# ProProject___V1_2024-08-05.net
KiCad netlist of a schematic drawn in EasyEDA Pro
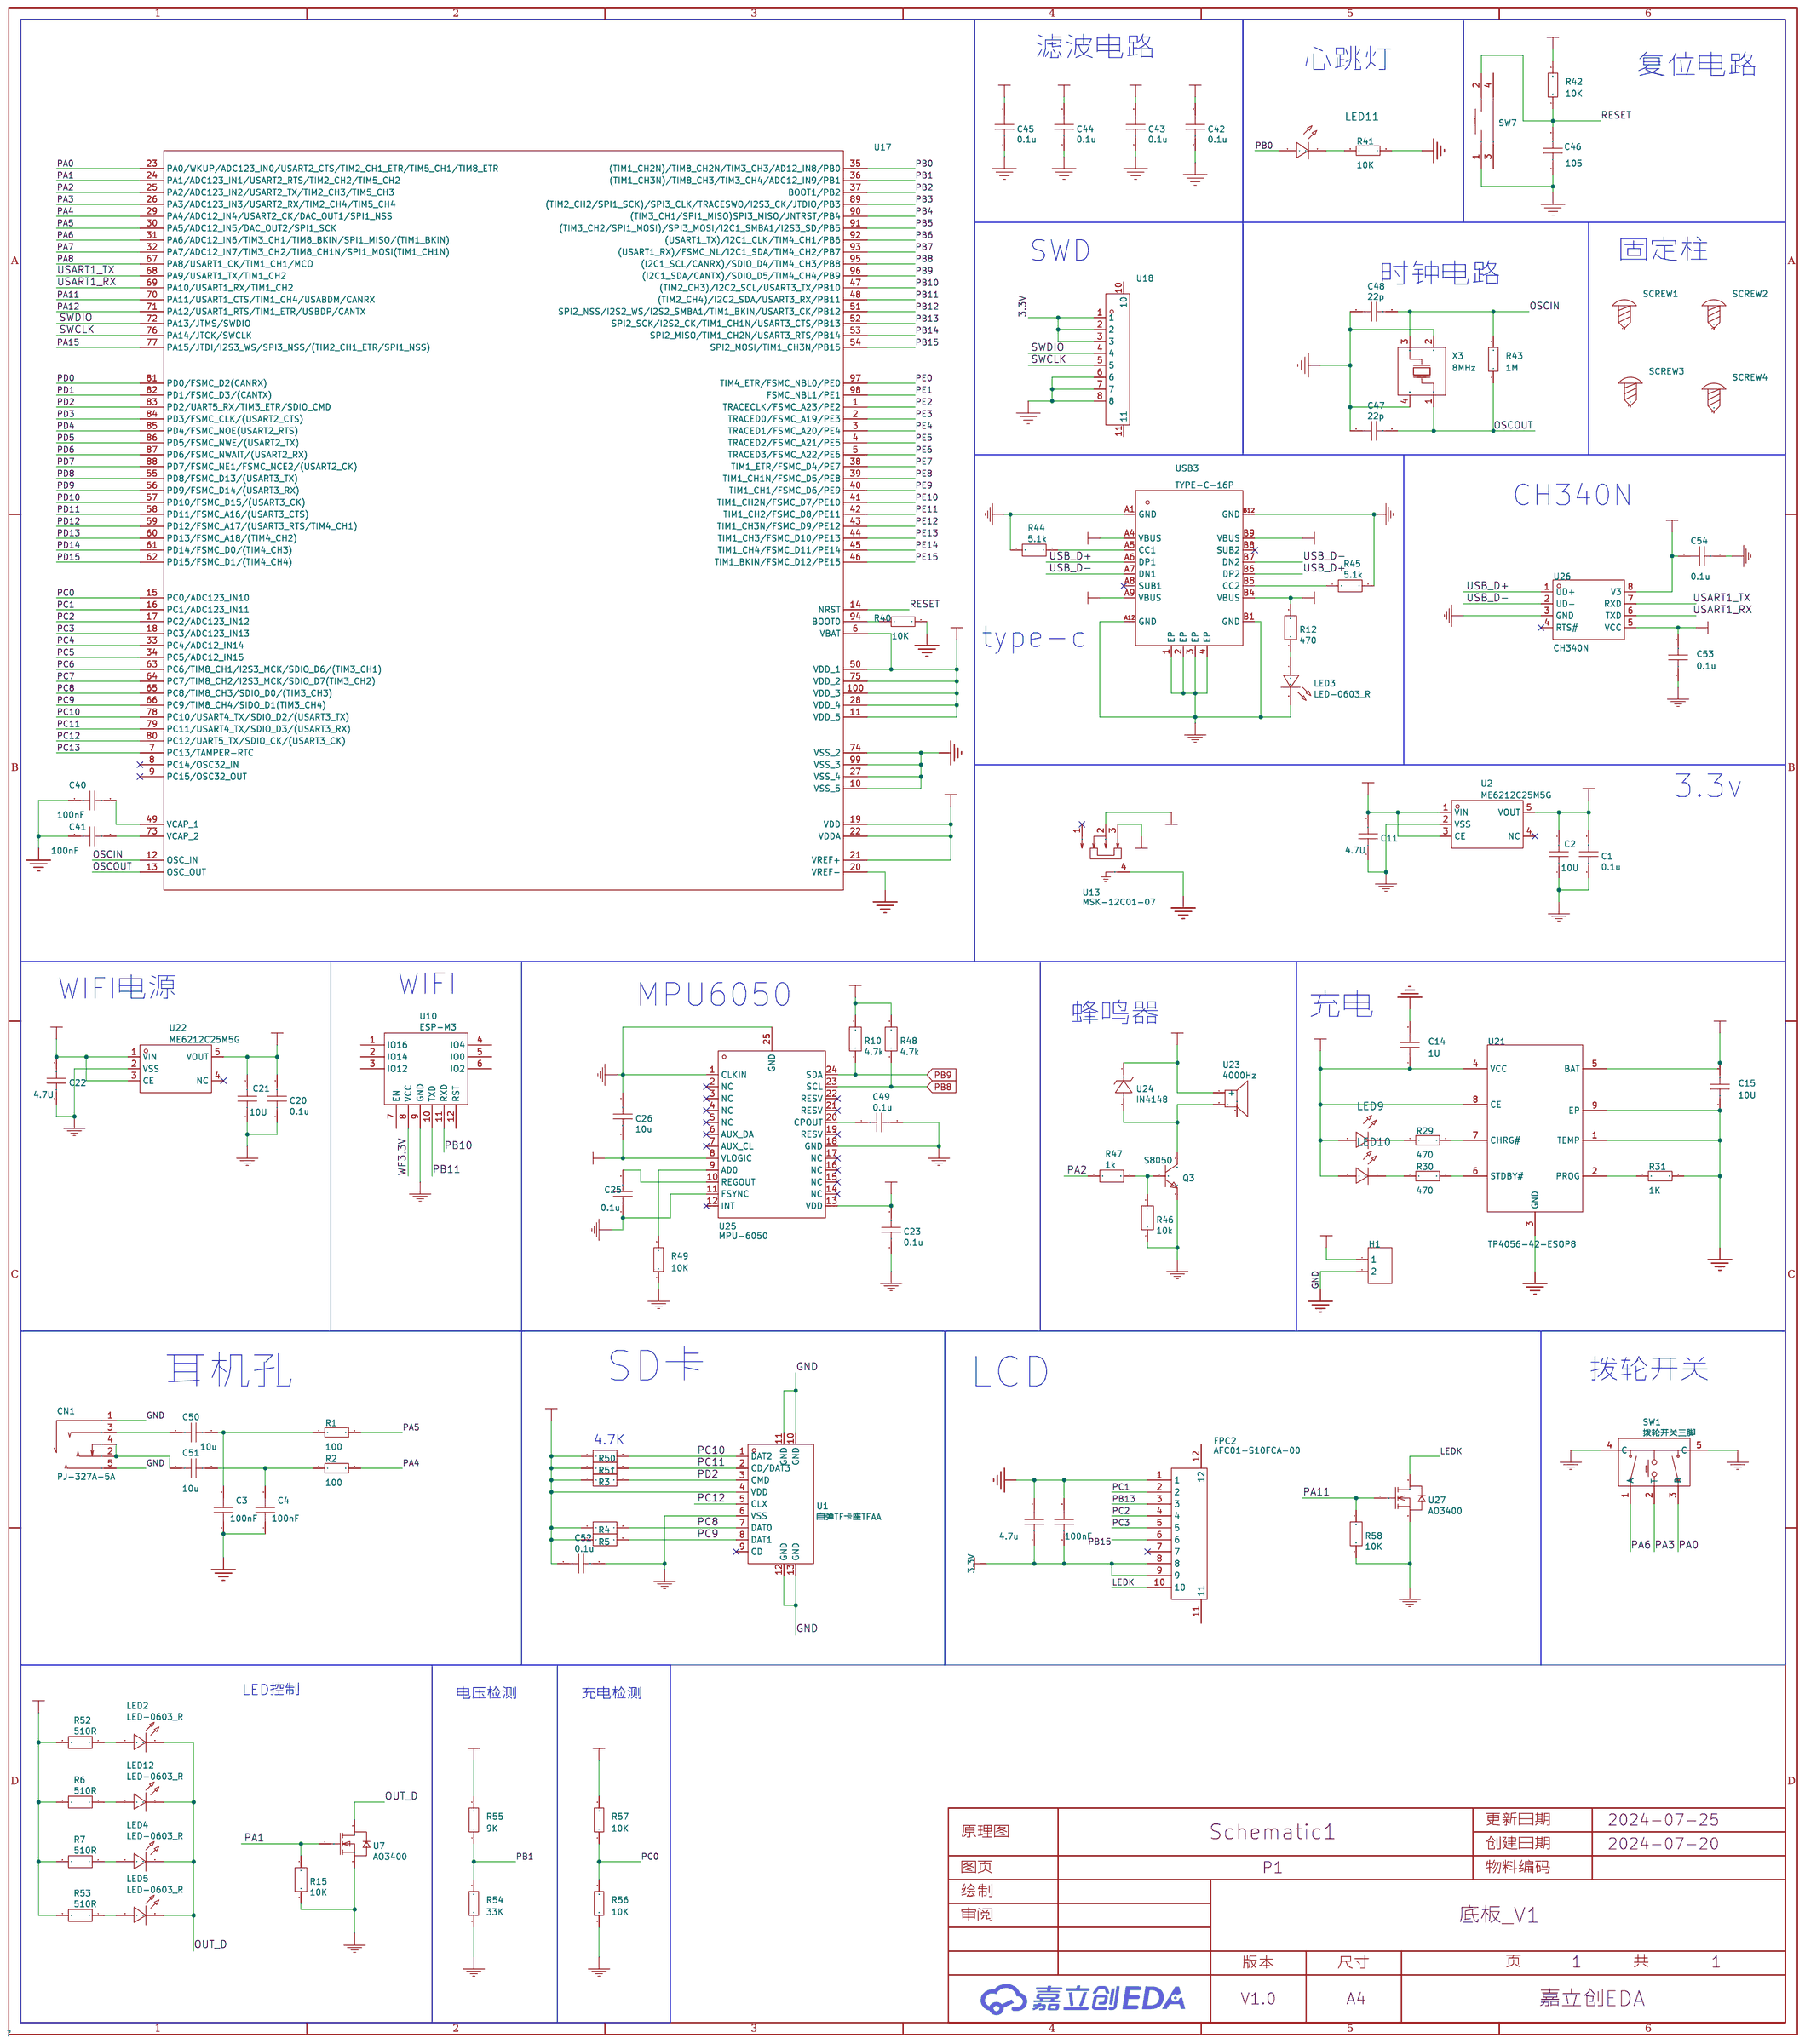
[diagram p0: schematic sheet]

(export (version "E")
  (design (tool "Eeschema 10.0.6"))
  (components
    (comp (ref "C1")
      (value "0.1u")
      (footprint "easyedapro:footprint_d063")
      (libsource (lib "easyedapro") (part "0.1u"))
    )
    (comp (ref "C2")
      (value "10U")
      (footprint "easyedapro:footprint_d063")
      (libsource (lib "easyedapro") (part "10U"))
    )
    (comp (ref "C3")
      (value "100nF")
      (footprint "easyedapro:C0603")
      (libsource (lib "easyedapro") (part "CapAcitance"))
    )
    (comp (ref "C4")
      (value "100nF")
      (footprint "easyedapro:C0603")
      (libsource (lib "easyedapro") (part "CapAcitance"))
    )
    (comp (ref "C11")
      (value "4.7U")
      (footprint "easyedapro:footprint_d063")
      (libsource (lib "easyedapro") (part "4.7U"))
    )
    (comp (ref "C14")
      (value "1U")
      (footprint "easyedapro:C0603")
      (libsource (lib "easyedapro") (part "CapAcitance"))
    )
    (comp (ref "C15")
      (value "10U")
      (footprint "easyedapro:C0603")
      (libsource (lib "easyedapro") (part "CapAcitance"))
    )
    (comp (ref "C20")
      (value "0.1u")
      (footprint "easyedapro:footprint_d063")
      (libsource (lib "easyedapro") (part "0.1u"))
    )
    (comp (ref "C21")
      (value "10U")
      (footprint "easyedapro:footprint_d063")
      (libsource (lib "easyedapro") (part "10U"))
    )
    (comp (ref "C22")
      (value "4.7U")
      (footprint "easyedapro:footprint_d063")
      (libsource (lib "easyedapro") (part "4.7U"))
    )
    (comp (ref "C23")
      (value "0.1u")
      (footprint "easyedapro:footprint_d063")
      (libsource (lib "easyedapro") (part "0.1u"))
    )
    (comp (ref "C25")
      (value "0.1u")
      (footprint "easyedapro:footprint_d063")
      (libsource (lib "easyedapro") (part "0.1u"))
    )
    (comp (ref "C26")
      (value "10u")
      (footprint "easyedapro:footprint_d063")
      (libsource (lib "easyedapro") (part "10u"))
    )
    (comp (ref "C40")
      (value "100nF")
      (footprint "easyedapro:C0603")
      (libsource (lib "easyedapro") (part "CapAcitance"))
    )
    (comp (ref "C41")
      (value "100nF")
      (footprint "easyedapro:C0603")
      (libsource (lib "easyedapro") (part "CapAcitance"))
    )
    (comp (ref "C42")
      (value "0.1u")
      (footprint "easyedapro:footprint_88df")
      (libsource (lib "easyedapro") (part "1u"))
    )
    (comp (ref "C43")
      (value "0.1u")
      (footprint "easyedapro:footprint_88df")
      (libsource (lib "easyedapro") (part "1u"))
    )
    (comp (ref "C44")
      (value "0.1u")
      (footprint "easyedapro:footprint_88df")
      (libsource (lib "easyedapro") (part "1u"))
    )
    (comp (ref "C45")
      (value "0.1u")
      (footprint "easyedapro:footprint_88df")
      (libsource (lib "easyedapro") (part "1u"))
    )
    (comp (ref "C46")
      (value "105")
      (footprint "easyedapro:footprint_88df")
      (libsource (lib "easyedapro") (part "105"))
    )
    (comp (ref "C47")
      (value "22p")
      (footprint "easyedapro:footprint_88df")
      (libsource (lib "easyedapro") (part "22p"))
    )
    (comp (ref "C48")
      (value "22p")
      (footprint "easyedapro:footprint_88df")
      (libsource (lib "easyedapro") (part "22p"))
    )
    (comp (ref "C49")
      (value "0.1u")
      (footprint "easyedapro:footprint_d063")
      (libsource (lib "easyedapro") (part "0.1u"))
    )
    (comp (ref "C50")
      (value "10u")
      (footprint "easyedapro:C0603")
      (libsource (lib "easyedapro") (part "CapAcitance"))
    )
    (comp (ref "C51")
      (value "10u")
      (footprint "easyedapro:C0603")
      (libsource (lib "easyedapro") (part "CapAcitance"))
    )
    (comp (ref "C52")
      (value "0.1u")
      (footprint "easyedapro:C0603")
      (libsource (lib "easyedapro") (part "0.1u"))
    )
    (comp (ref "C53")
      (value "0.1u")
      (footprint "easyedapro:footprint_d063")
      (libsource (lib "easyedapro") (part "0.1u"))
    )
    (comp (ref "C54")
      (value "0.1u")
      (footprint "easyedapro:footprint_d063")
      (libsource (lib "easyedapro") (part "0.1u"))
    )
    (comp (ref "C57")
      (value "100nF")
      (footprint "easyedapro:C0603")
      (libsource (lib "easyedapro") (part "CapAcitance"))
    )
    (comp (ref "C58")
      (value "4.7u")
      (footprint "easyedapro:C0603")
      (libsource (lib "easyedapro") (part "CapAcitance"))
    )
    (comp (ref "CN1")
      (value "PJ-327A-5A")
      (footprint "easyedapro:AUDIO-SMD_PJ-327A-5A")
      (description "连接器类型:3.5mm耳机座;额定电流:500mA;额定电压:30V;工作温度范围:-40°C~+80°C;")
      (fields (field (name "Manufacturer") "韩国韩荣"))
      (libsource (lib "easyedapro") (part "PJ-327A-5A"))
    )
    (comp (ref "FPC2")
      (value "AFC01-S10FCA-00")
      (footprint "easyedapro:FPC-SMD_P0.5-10P_FGS-XJ-H2.0")
      (description "锁定特性:翻盖式;触点类型:下接;触点数量:10P;间距:0.5mm;安装类型:卧贴;")
      (fields (field (name "Manufacturer") "JS(钜硕电子)"))
      (libsource (lib "easyedapro") (part "AFC01-S10FCA-00"))
    )
    (comp (ref "H1")
      (value "~")
      (footprint "easyedapro:HDR-TH_2P-P2.54-V-F")
      (libsource (lib "easyedapro") (part "Header-Female-2.54_1x2"))
    )
    (comp (ref "LED2")
      (value "LED-0603_R")
      (footprint "easyedapro:footprint_5b50")
      (fields
        (field (name "Manufacturer Part") "19-217/R6C-AL1M2VY/3T")
        (field (name "Manufacturer") "EVERLIGHT(台湾亿光)")
      )
      (libsource (lib "easyedapro") (part "LED-0603_R"))
    )
    (comp (ref "LED3")
      (value "LED-0603_R")
      (footprint "easyedapro:footprint_1210")
      (fields
        (field (name "Manufacturer Part") "19-217/R6C-AL1M2VY/3T")
        (field (name "Manufacturer") "EVERLIGHT(台湾亿光)")
      )
      (libsource (lib "easyedapro") (part "LED-0603_R"))
    )
    (comp (ref "LED4")
      (value "LED-0603_R")
      (footprint "easyedapro:footprint_5b50")
      (fields
        (field (name "Manufacturer Part") "19-217/R6C-AL1M2VY/3T")
        (field (name "Manufacturer") "EVERLIGHT(台湾亿光)")
      )
      (libsource (lib "easyedapro") (part "LED-0603_R"))
    )
    (comp (ref "LED5")
      (value "LED-0603_R")
      (footprint "easyedapro:footprint_5b50")
      (fields
        (field (name "Manufacturer Part") "19-217/R6C-AL1M2VY/3T")
        (field (name "Manufacturer") "EVERLIGHT(台湾亿光)")
      )
      (libsource (lib "easyedapro") (part "LED-0603_R"))
    )
    (comp (ref "LED9")
      (value "~")
      (footprint "easyedapro:LED_0603")
      (libsource (lib "easyedapro") (part "LED_R"))
    )
    (comp (ref "LED10")
      (value "~")
      (footprint "easyedapro:LED_0603")
      (libsource (lib "easyedapro") (part "LED_R"))
    )
    (comp (ref "LED11")
      (value "~")
      (footprint "easyedapro:LED_0603")
      (libsource (lib "easyedapro") (part "LED_R"))
    )
    (comp (ref "LED12")
      (value "LED-0603_R")
      (footprint "easyedapro:footprint_5b50")
      (fields
        (field (name "Manufacturer Part") "19-217/R6C-AL1M2VY/3T")
        (field (name "Manufacturer") "EVERLIGHT(台湾亿光)")
      )
      (libsource (lib "easyedapro") (part "LED-0603_R"))
    )
    (comp (ref "Q3")
      (value "S8050")
      (footprint "easyedapro:footprint_2907")
      (fields (field (name "Manufacturer") "集晶电子"))
      (libsource (lib "easyedapro") (part "S8050"))
    )
    (comp (ref "R1") (value "100") (footprint "easyedapro:R0805") (libsource (lib "easyedapro") (part "电阻")))
    (comp (ref "R2") (value "100") (footprint "easyedapro:R0805") (libsource (lib "easyedapro") (part "电阻")))
    (comp (ref "R3") (value "1k") (footprint "easyedapro:R0805") (libsource (lib "easyedapro") (part "1k")))
    (comp (ref "R4") (value "1k") (footprint "easyedapro:R0805") (libsource (lib "easyedapro") (part "1k")))
    (comp (ref "R5") (value "1k") (footprint "easyedapro:R0805") (libsource (lib "easyedapro") (part "1k")))
    (comp (ref "R6")
      (value "510R")
      (footprint "easyedapro:footprint_4dfc")
      (libsource (lib "easyedapro") (part "510R"))
    )
    (comp (ref "R7")
      (value "510R")
      (footprint "easyedapro:footprint_4dfc")
      (libsource (lib "easyedapro") (part "510R"))
    )
    (comp (ref "R10")
      (value "4.7k")
      (footprint "easyedapro:footprint_1dde")
      (libsource (lib "easyedapro") (part "4.7k"))
    )
    (comp (ref "R12")
      (value "470")
      (footprint "easyedapro:footprint_1dde")
      (libsource (lib "easyedapro") (part "470"))
    )
    (comp (ref "R15")
      (value "10K")
      (footprint "easyedapro:footprint_4dfc")
      (libsource (lib "easyedapro") (part "10K"))
    )
    (comp (ref "R29") (value "470") (footprint "easyedapro:R0805") (libsource (lib "easyedapro") (part "电阻")))
    (comp (ref "R30") (value "470") (footprint "easyedapro:R0805") (libsource (lib "easyedapro") (part "电阻")))
    (comp (ref "R31") (value "1K") (footprint "easyedapro:R0805") (libsource (lib "easyedapro") (part "电阻")))
    (comp (ref "R40") (value "10K") (footprint "easyedapro:R0805") (libsource (lib "easyedapro") (part "电阻")))
    (comp (ref "R41") (value "10K") (footprint "easyedapro:R0805") (libsource (lib "easyedapro") (part "电阻")))
    (comp (ref "R42") (value "10K") (footprint "easyedapro:R0805") (libsource (lib "easyedapro") (part "电阻")))
    (comp (ref "R43") (value "1M") (footprint "easyedapro:R0805") (libsource (lib "easyedapro") (part "电阻")))
    (comp (ref "R44")
      (value "5.1k")
      (footprint "easyedapro:footprint_1dde")
      (libsource (lib "easyedapro") (part "5.1k"))
    )
    (comp (ref "R45")
      (value "5.1k")
      (footprint "easyedapro:footprint_1dde")
      (libsource (lib "easyedapro") (part "5.1k"))
    )
    (comp (ref "R46")
      (value "10k")
      (footprint "easyedapro:footprint_b185")
      (libsource (lib "easyedapro") (part "00k"))
    )
    (comp (ref "R47")
      (value "1k")
      (footprint "easyedapro:footprint_b185")
      (libsource (lib "easyedapro") (part "1k"))
    )
    (comp (ref "R48")
      (value "4.7k")
      (footprint "easyedapro:footprint_1dde")
      (libsource (lib "easyedapro") (part "4.7k"))
    )
    (comp (ref "R49") (value "10K") (footprint "easyedapro:R0805") (libsource (lib "easyedapro") (part "电阻")))
    (comp (ref "R50") (value "1k") (footprint "easyedapro:R0805") (libsource (lib "easyedapro") (part "1k")))
    (comp (ref "R51") (value "1k") (footprint "easyedapro:R0805") (libsource (lib "easyedapro") (part "1k")))
    (comp (ref "R52")
      (value "510R")
      (footprint "easyedapro:footprint_4dfc")
      (libsource (lib "easyedapro") (part "510R"))
    )
    (comp (ref "R53")
      (value "510R")
      (footprint "easyedapro:footprint_4dfc")
      (libsource (lib "easyedapro") (part "510R"))
    )
    (comp (ref "R54") (value "33K") (footprint "easyedapro:R0805") (libsource (lib "easyedapro") (part "电阻")))
    (comp (ref "R55") (value "9K") (footprint "easyedapro:R0805") (libsource (lib "easyedapro") (part "电阻")))
    (comp (ref "R56") (value "10K") (footprint "easyedapro:R0805") (libsource (lib "easyedapro") (part "电阻")))
    (comp (ref "R57") (value "10K") (footprint "easyedapro:R0805") (libsource (lib "easyedapro") (part "电阻")))
    (comp (ref "R58")
      (value "10K")
      (footprint "easyedapro:footprint_4dfc")
      (libsource (lib "easyedapro") (part "10K"))
    )
    (comp (ref "SCREW1")
      (value "~")
      (footprint "easyedapro:M3螺丝")
      (libsource (lib "easyedapro") (part "螺丝孔"))
    )
    (comp (ref "SCREW2")
      (value "~")
      (footprint "easyedapro:M3螺丝")
      (libsource (lib "easyedapro") (part "螺丝孔"))
    )
    (comp (ref "SCREW3")
      (value "~")
      (footprint "easyedapro:M3螺丝")
      (libsource (lib "easyedapro") (part "螺丝孔"))
    )
    (comp (ref "SCREW4")
      (value "~")
      (footprint "easyedapro:M3螺丝")
      (libsource (lib "easyedapro") (part "螺丝孔"))
    )
    (comp (ref "SW1")
      (value "拨轮开关三脚")
      (footprint "easyedapro:footprint_864c")
      (libsource (lib "easyedapro") (part "拨轮开关三脚"))
    )
    (comp (ref "SW7")
      (value "K2-1806SA-C4DW-04")
      (footprint "easyedapro:footprint_8ca7")
      (fields (field (name "Manufacturer") "韩国韩荣"))
      (libsource (lib "easyedapro") (part "K2-1806SA-C4DW-04"))
    )
    (comp (ref "U1")
      (value "自弹TF卡座TFAA")
      (footprint "easyedapro:SIM-SMD_C9900015645")
      (libsource (lib "easyedapro") (part "自弹TF卡座TFAA"))
    )
    (comp (ref "U2")
      (value "ME6212C25M5G")
      (footprint "easyedapro:footprint_203e")
      (fields (field (name "Manufacturer") "MICRONE(南京微盟)"))
      (libsource (lib "easyedapro") (part "ME6212C25M5G"))
    )
    (comp (ref "U7")
      (value "AO3400")
      (footprint "easyedapro:footprint_8e82")
      (fields (field (name "Manufacturer") "ElecSuper(静芯微）"))
      (libsource (lib "easyedapro") (part "AO3400"))
    )
    (comp (ref "U10")
      (value "ESP-M3")
      (footprint "easyedapro:footprint_c8ca")
      (libsource (lib "easyedapro") (part "ESP-M3"))
    )
    (comp (ref "U13")
      (value "MSK-12C01-07")
      (footprint "easyedapro:SW-SMD_MSK12CO2-BDM")
      (libsource (lib "easyedapro") (part "MSK-12C01-07"))
    )
    (comp (ref "U17")
      (value "~")
      (footprint "easyedapro:LQFP-100_L14.0-W14.0-P0.50-LS16.0-BL")
      (fields (field (name "Manufacturer Part") "STM32F407VET6") (field (name "Manufacturer") "ST"))
      (libsource (lib "easyedapro") (part "STM32F407VET6"))
    )
    (comp (ref "U18")
      (value "SMTFPC连接器0.5MM间距翻盖8PIN")
      (footprint "easyedapro:FPC-SMD_AFC01-S08FCC-00")
      (libsource (lib "easyedapro") (part "SMTFPC连接器0.5MM间距翻盖8PIN"))
    )
    (comp (ref "U21")
      (value "TP4056-42-ESOP8")
      (footprint "easyedapro:ESOP-8_L4.9-W3.9-P1.27-LS6.0-BL-EP")
      (description "充电电池的类型:-;电池单元组数:-;最大充电电流:-;充满的电池组电压:-;最大供应电压:-;")
      (fields (field (name "Manufacturer") "TOPPOWER(南京拓微)"))
      (libsource (lib "easyedapro") (part "TP4056"))
    )
    (comp (ref "U22")
      (value "ME6212C25M5G")
      (footprint "easyedapro:footprint_203e")
      (fields (field (name "Manufacturer") "MICRONE(南京微盟)"))
      (libsource (lib "easyedapro") (part "ME6212C25M5G"))
    )
    (comp (ref "U23")
      (value "4000Hz")
      (footprint "easyedapro:footprint_ea09")
      (fields (field (name "Manufacturer Part") "YX-SMD5020") (field (name "Manufacturer") "YUEXIN(悦馨)"))
      (libsource (lib "easyedapro") (part "4000Hz"))
    )
    (comp (ref "U24")
      (value "IN4148")
      (footprint "easyedapro:footprint_0926")
      (fields (field (name "Manufacturer Part") "IN4148贴片二极管"))
      (libsource (lib "easyedapro") (part "IN4148"))
    )
    (comp (ref "U25")
      (value "MPU-6050")
      (footprint "easyedapro:QFN-24_L4.0-W4.0-P0.50-BL-EP2.7")
      (description "三轴加速度计和三轴陀螺仪，工作电压：2.375V~3.46V")
      (fields (field (name "Manufacturer") "TDK InvenSense(应美盛)"))
      (libsource (lib "easyedapro") (part "MPU-6050_C24112"))
    )
    (comp (ref "U26")
      (value "CH340N")
      (footprint "easyedapro:SOP-8_L4.9-W3.9-P1.27-LS6.0-BL")
      (fields (field (name "Manufacturer") "WCH(南京沁恒)"))
      (libsource (lib "easyedapro") (part "CH340N_C2977777"))
    )
    (comp (ref "U27")
      (value "AO3400")
      (footprint "easyedapro:footprint_8e82")
      (fields (field (name "Manufacturer") "ElecSuper(静芯微）"))
      (libsource (lib "easyedapro") (part "AO3400"))
    )
    (comp (ref "USB3")
      (value "TYPE-C-16P")
      (footprint "easyedapro:footprint_feef")
      (fields
        (field (name "Manufacturer Part") "KH-TYPE-C-16P")
        (field (name "Manufacturer") "Shenzhen Kinghelm Elec")
      )
      (libsource (lib "easyedapro") (part "TYPE-C-16P"))
    )
    (comp (ref "X3")
      (value "8MHz")
      (footprint "easyedapro:OSC-SMD_4P-L3.2-W2.5-BL")
      (description "晶振类型:贴片无源晶振;频率:25MHz;频率公差:±10ppm;频率稳定度:±30ppm;负载电容:12pF;工作温度:-40°C~+85°C;")
      (fields (field (name "Manufacturer Part") "X322525MOB4SI") (field (name "Manufacturer") "YXC(扬兴晶振)"))
      (libsource (lib "easyedapro") (part "X322525MOB4SI"))
    )
  )
  (nets
    (net (code "1") (name "/LEDK") (class "Default")
      (node (ref "FPC2") (pin "10") (pinfunction "10_10") (pintype "unspecified"))
      (node (ref "U27") (pin "3") (pinfunction "D_3") (pintype "unspecified"))
    )
    (net (code "2") (name "/OSCIN") (class "Default")
      (node (ref "C48") (pin "2") (pinfunction "2_2") (pintype "unspecified"))
      (node (ref "R43") (pin "2") (pinfunction "2_2") (pintype "input"))
      (node (ref "U17") (pin "12") (pinfunction "OSC_IN_12") (pintype "input"))
      (node (ref "X3") (pin "3") (pinfunction "OSC2_3") (pintype "input"))
    )
    (net (code "3") (name "/OSCOUT") (class "Default")
      (node (ref "C47") (pin "2") (pinfunction "2_2") (pintype "unspecified"))
      (node (ref "R43") (pin "1") (pinfunction "1_1") (pintype "input"))
      (node (ref "U17") (pin "13") (pinfunction "OSC_OUT_13") (pintype "input"))
      (node (ref "X3") (pin "1") (pinfunction "OSC1_1") (pintype "input"))
    )
    (net (code "4") (name "/OUT_D") (class "Default")
      (node (ref "LED12") (pin "2") (pinfunction "2_2") (pintype "unspecified"))
      (node (ref "LED2") (pin "2") (pinfunction "2_2") (pintype "unspecified"))
      (node (ref "LED4") (pin "2") (pinfunction "2_2") (pintype "unspecified"))
      (node (ref "LED5") (pin "2") (pinfunction "2_2") (pintype "unspecified"))
      (node (ref "U7") (pin "3") (pinfunction "D_3") (pintype "unspecified"))
    )
    (net (code "5") (name "/PA0") (class "Default")
      (node (ref "SW1") (pin "3") (pinfunction "B_3") (pintype "unspecified"))
      (node (ref "U17") (pin "23") (pinfunction "PA0/WKUP/ADC123_IN0/USART2_CTS/TIM2_CH1_ETR/TIM5_CH1/TIM8_ETR_23") (pintype "input"))
    )
    (net (code "6") (name "/PA1") (class "Default")
      (node (ref "R15") (pin "2") (pinfunction "2_2") (pintype "unspecified"))
      (node (ref "U17") (pin "24") (pinfunction "PA1/ADC123_IN1/USART2_RTS/TIM2_CH2/TIM5_CH2_24") (pintype "input"))
      (node (ref "U7") (pin "1") (pinfunction "G_1") (pintype "unspecified"))
    )
    (net (code "7") (name "/PA2") (class "Default")
      (node (ref "R47") (pin "1") (pinfunction "1_1") (pintype "unspecified"))
      (node (ref "U17") (pin "25") (pinfunction "PA2/ADC123_IN2/USART2_TX/TIM2_CH3/TIM5_CH3_25") (pintype "input"))
    )
    (net (code "8") (name "/PA3") (class "Default")
      (node (ref "SW1") (pin "2") (pinfunction "T_2") (pintype "unspecified"))
      (node (ref "U17") (pin "26") (pinfunction "PA3/ADC123_IN3/USART2_RX/TIM2_CH4/TIM5_CH4_26") (pintype "input"))
    )
    (net (code "9") (name "/PA4") (class "Default")
      (node (ref "R2") (pin "2") (pinfunction "2_2") (pintype "input"))
      (node (ref "U17") (pin "29") (pinfunction "PA4/ADC12_IN4/USART2_CK/DAC_OUT1/SPI1_NSS_29") (pintype "input"))
    )
    (net (code "10") (name "/PA5") (class "Default")
      (node (ref "R1") (pin "2") (pinfunction "2_2") (pintype "input"))
      (node (ref "U17") (pin "30") (pinfunction "PA5/ADC12_IN5/DAC_OUT2/SPI1_SCK_30") (pintype "input"))
    )
    (net (code "11") (name "/PA6") (class "Default")
      (node (ref "SW1") (pin "1") (pinfunction "A_1") (pintype "unspecified"))
      (node (ref "U17") (pin "31") (pinfunction "PA6/ADC12_IN6/TIM3_CH1/TIM8_BKIN/SPI1_MISO/(TIM1_BKIN)_31") (pintype "input"))
    )
    (net (code "12") (name "/PA7") (class "Default")
      (node (ref "U17") (pin "32") (pinfunction "PA7/ADC12_IN7/TIM3_CH2/TIM8_CH1N/SPI1_MOSI(TIM1_CH1N)_32") (pintype "input"))
    )
    (net (code "13") (name "/PA8") (class "Default")
      (node (ref "U17") (pin "67") (pinfunction "PA8/USART1_CK/TIM1_CH1/MCO_67") (pintype "input"))
    )
    (net (code "14") (name "/PA11") (class "Default")
      (node (ref "R58") (pin "2") (pinfunction "2_2") (pintype "unspecified"))
      (node (ref "U17") (pin "70") (pinfunction "PA11/USART1_CTS/TIM1_CH4/USABDM/CANRX_70") (pintype "input"))
      (node (ref "U27") (pin "1") (pinfunction "G_1") (pintype "unspecified"))
    )
    (net (code "15") (name "/PA12") (class "Default")
      (node (ref "U17") (pin "71") (pinfunction "PA12/USART1_RTS/TIM1_ETR/USBDP/CANTX_71") (pintype "input"))
    )
    (net (code "16") (name "/PA15") (class "Default")
      (node (ref "U17") (pin "77") (pinfunction "PA15/JTDI/I2S3_WS/SPI3_NSS/(TIM2_CH1_ETR/SPI1_NSS)_77") (pintype "input"))
    )
    (net (code "17") (name "/PB0") (class "Default")
      (node (ref "LED11") (pin "2") (pinfunction "A_2") (pintype "input"))
      (node (ref "U17") (pin "35") (pinfunction "(TIM1_CH2N)/TIM8_CH2N/TIM3_CH3/AD12_IN8/PB0_35") (pintype "input"))
    )
    (net (code "18") (name "/PB1") (class "Default")
      (node (ref "R54") (pin "2") (pinfunction "2_2") (pintype "input"))
      (node (ref "R55") (pin "1") (pinfunction "1_1") (pintype "input"))
      (node (ref "U17") (pin "36") (pinfunction "(TIM1_CH3N)/TIM8_CH3/TIM3_CH4/ADC12_IN9/PB1_36") (pintype "input"))
    )
    (net (code "19") (name "/PB2") (class "Default")
      (node (ref "U17") (pin "37") (pinfunction "BOOT1/PB2_37") (pintype "input"))
    )
    (net (code "20") (name "/PB3") (class "Default")
      (node (ref "U17") (pin "89") (pinfunction "(TIM2_CH2/SPI1_SCK)/SPI3_CLK/TRACESWO/I2S3_CK/JTDIO/PB3_89") (pintype "input"))
    )
    (net (code "21") (name "/PB4") (class "Default")
      (node (ref "U17") (pin "90") (pinfunction "(TIM3_CH1/SPI1_MISO)SPI3_MISO/JNTRST/PB4_90") (pintype "input"))
    )
    (net (code "22") (name "/PB5") (class "Default")
      (node (ref "U17") (pin "91") (pinfunction "(TIM3_CH2/SPI1_MOSI)/SPI3_MOSI/I2C1_SMBA1/I2S3_SD/PB5_91") (pintype "input"))
    )
    (net (code "23") (name "/PB6") (class "Default")
      (node (ref "U17") (pin "92") (pinfunction "(USART1_TX)/I2C1_CLK/TIM4_CH1/PB6_92") (pintype "input"))
    )
    (net (code "24") (name "/PB7") (class "Default")
      (node (ref "U17") (pin "93") (pinfunction "(USART1_RX)/FSMC_NL/I2C1_SDA/TIM4_CH2/PB7_93") (pintype "input"))
    )
    (net (code "25") (name "/PB10") (class "Default")
      (node (ref "U10") (pin "11") (pinfunction "RXD_11") (pintype "unspecified"))
      (node (ref "U17") (pin "47") (pinfunction "(TIM2_CH3)/I2C2_SCL/USART3_TX/PB10_47") (pintype "input"))
    )
    (net (code "26") (name "/PB11") (class "Default")
      (node (ref "U10") (pin "10") (pinfunction "TXD_10") (pintype "unspecified"))
      (node (ref "U17") (pin "48") (pinfunction "(TIM2_CH4)/I2C2_SDA/USART3_RX/PB11_48") (pintype "input"))
    )
    (net (code "27") (name "/PB12") (class "Default")
      (node (ref "U17") (pin "51") (pinfunction "SPI2_NSS/I2S2_WS/I2S2_SMBA1/TIM1_BKIN/USART3_CK/PB12_51") (pintype "input"))
    )
    (net (code "28") (name "/PB13") (class "Default")
      (node (ref "FPC2") (pin "3") (pinfunction "3_3") (pintype "unspecified"))
      (node (ref "U17") (pin "52") (pinfunction "SPI2_SCK/I2S2_CK/TIM1_CH1N/USART3_CTS/PB13_52") (pintype "input"))
    )
    (net (code "29") (name "/PB14") (class "Default")
      (node (ref "U17") (pin "53") (pinfunction "SPI2_MISO/TIM1_CH2N/USART3_RTS/PB14_53") (pintype "input"))
    )
    (net (code "30") (name "/PB15") (class "Default")
      (node (ref "FPC2") (pin "6") (pinfunction "6_6") (pintype "unspecified"))
      (node (ref "U17") (pin "54") (pinfunction "SPI2_MOSI/TIM1_CH3N/PB15_54") (pintype "input"))
    )
    (net (code "31") (name "/PC0") (class "Default")
      (node (ref "R56") (pin "2") (pinfunction "2_2") (pintype "input"))
      (node (ref "R57") (pin "1") (pinfunction "1_1") (pintype "input"))
      (node (ref "U17") (pin "15") (pinfunction "PC0/ADC123_IN10_15") (pintype "input"))
    )
    (net (code "32") (name "/PC1") (class "Default")
      (node (ref "FPC2") (pin "2") (pinfunction "2_2") (pintype "unspecified"))
      (node (ref "U17") (pin "16") (pinfunction "PC1/ADC123_IN11_16") (pintype "input"))
    )
    (net (code "33") (name "/PC2") (class "Default")
      (node (ref "FPC2") (pin "4") (pinfunction "4_4") (pintype "unspecified"))
      (node (ref "U17") (pin "17") (pinfunction "PC2/ADC123_IN12_17") (pintype "input"))
    )
    (net (code "34") (name "/PC3") (class "Default")
      (node (ref "FPC2") (pin "5") (pinfunction "5_5") (pintype "unspecified"))
      (node (ref "U17") (pin "18") (pinfunction "PC3/ADC123_IN13_18") (pintype "input"))
    )
    (net (code "35") (name "/PC4") (class "Default")
      (node (ref "U17") (pin "33") (pinfunction "PC4/ADC12_IN14_33") (pintype "input"))
    )
    (net (code "36") (name "/PC5") (class "Default")
      (node (ref "U17") (pin "34") (pinfunction "PC5/ADC12_IN15_34") (pintype "input"))
    )
    (net (code "37") (name "/PC6") (class "Default")
      (node (ref "U17") (pin "63") (pinfunction "PC6/TIM8_CH1/I2S3_MCK/SDIO_D6/(TIM3_CH1)_63") (pintype "input"))
    )
    (net (code "38") (name "/PC7") (class "Default")
      (node (ref "U17") (pin "64") (pinfunction "PC7/TIM8_CH2/I2S3_MCK/SDIO_D7(TIM3_CH2)_64") (pintype "input"))
    )
    (net (code "39") (name "/PC8") (class "Default")
      (node (ref "R4") (pin "2") (pinfunction "2_2") (pintype "unspecified"))
      (node (ref "U1") (pin "7") (pinfunction "DAT0_7") (pintype "unspecified"))
      (node (ref "U17") (pin "65") (pinfunction "PC8/TIM8_CH3/SDIO_D0/(TIM3_CH3)_65") (pintype "input"))
    )
    (net (code "40") (name "/PC9") (class "Default")
      (node (ref "R5") (pin "2") (pinfunction "2_2") (pintype "unspecified"))
      (node (ref "U1") (pin "8") (pinfunction "DAT1_8") (pintype "unspecified"))
      (node (ref "U17") (pin "66") (pinfunction "PC9/TIM8_CH4/SIDO_D1(TIM3_CH4)_66") (pintype "input"))
    )
    (net (code "41") (name "/PC10") (class "Default")
      (node (ref "R50") (pin "2") (pinfunction "2_2") (pintype "unspecified"))
      (node (ref "U1") (pin "1") (pinfunction "DAT2_1") (pintype "unspecified"))
      (node (ref "U17") (pin "78") (pinfunction "PC10/USART4_TX/SDIO_D2/(USART3_TX)_78") (pintype "input"))
    )
    (net (code "42") (name "/PC11") (class "Default")
      (node (ref "R51") (pin "2") (pinfunction "2_2") (pintype "unspecified"))
      (node (ref "U1") (pin "2") (pinfunction "CD/DAT3_2") (pintype "unspecified"))
      (node (ref "U17") (pin "79") (pinfunction "PC11/USART4_TX/SDIO_D3/(USART3_RX)_79") (pintype "input"))
    )
    (net (code "43") (name "/PC12") (class "Default")
      (node (ref "U1") (pin "5") (pinfunction "CLX_5") (pintype "unspecified"))
      (node (ref "U17") (pin "80") (pinfunction "PC12/UART5_TX/SDIO_CK/(USART3_CK)_80") (pintype "input"))
    )
    (net (code "44") (name "/PC13") (class "Default")
      (node (ref "U17") (pin "7") (pinfunction "PC13/TAMPER-RTC_7") (pintype "input"))
    )
    (net (code "45") (name "/PD0") (class "Default")
      (node (ref "U17") (pin "81") (pinfunction "PD0/FSMC_D2(CANRX)_81") (pintype "input"))
    )
    (net (code "46") (name "/PD1") (class "Default")
      (node (ref "U17") (pin "82") (pinfunction "PD1/FSMC_D3/(CANTX)_82") (pintype "input"))
    )
    (net (code "47") (name "/PD2") (class "Default")
      (node (ref "R3") (pin "2") (pinfunction "2_2") (pintype "unspecified"))
      (node (ref "U1") (pin "3") (pinfunction "CMD_3") (pintype "unspecified"))
      (node (ref "U17") (pin "83") (pinfunction "PD2/UART5_RX/TIM3_ETR/SDIO_CMD_83") (pintype "input"))
    )
    (net (code "48") (name "/PD3") (class "Default")
      (node (ref "U17") (pin "84") (pinfunction "PD3/FSMC_CLK/(USART2_CTS)_84") (pintype "input"))
    )
    (net (code "49") (name "/PD4") (class "Default")
      (node (ref "U17") (pin "85") (pinfunction "PD4/FSMC_NOE(USART2_RTS)_85") (pintype "input"))
    )
    (net (code "50") (name "/PD5") (class "Default")
      (node (ref "U17") (pin "86") (pinfunction "PD5/FSMC_NWE/(USART2_TX)_86") (pintype "input"))
    )
    (net (code "51") (name "/PD6") (class "Default")
      (node (ref "U17") (pin "87") (pinfunction "PD6/FSMC_NWAIT/(USART2_RX)_87") (pintype "input"))
    )
    (net (code "52") (name "/PD7") (class "Default")
      (node (ref "U17") (pin "88") (pinfunction "PD7/FSMC_NE1/FSMC_NCE2/(USART2_CK)_88") (pintype "input"))
    )
    (net (code "53") (name "/PD8") (class "Default")
      (node (ref "U17") (pin "55") (pinfunction "PD8/FSMC_D13/(USART3_TX)_55") (pintype "input"))
    )
    (net (code "54") (name "/PD9") (class "Default")
      (node (ref "U17") (pin "56") (pinfunction "PD9/FSMC_D14/(USART3_RX)_56") (pintype "input"))
    )
    (net (code "55") (name "/PD10") (class "Default")
      (node (ref "U17") (pin "57") (pinfunction "PD10/FSMC_D15/(USART3_CK)_57") (pintype "input"))
    )
    (net (code "56") (name "/PD11") (class "Default")
      (node (ref "U17") (pin "58") (pinfunction "PD11/FSMC_A16/(USART3_CTS)_58") (pintype "input"))
    )
    (net (code "57") (name "/PD12") (class "Default")
      (node (ref "U17") (pin "59") (pinfunction "PD12/FSMC_A17/(USART3_RTS/TIM4_CH1)_59") (pintype "input"))
    )
    (net (code "58") (name "/PD13") (class "Default")
      (node (ref "U17") (pin "60") (pinfunction "PD13/FSMC_A18/(TIM4_CH2)_60") (pintype "input"))
    )
    (net (code "59") (name "/PD14") (class "Default")
      (node (ref "U17") (pin "61") (pinfunction "PD14/FSMC_D0/(TIM4_CH3)_61") (pintype "input"))
    )
    (net (code "60") (name "/PD15") (class "Default")
      (node (ref "U17") (pin "62") (pinfunction "PD15/FSMC_D1/(TIM4_CH4)_62") (pintype "input"))
    )
    (net (code "61") (name "/PE0") (class "Default")
      (node (ref "U17") (pin "97") (pinfunction "TIM4_ETR/FSMC_NBL0/PE0_97") (pintype "input"))
    )
    (net (code "62") (name "/PE1") (class "Default")
      (node (ref "U17") (pin "98") (pinfunction "FSMC_NBL1/PE1_98") (pintype "input"))
    )
    (net (code "63") (name "/PE2") (class "Default")
      (node (ref "U17") (pin "1") (pinfunction "TRACECLK/FSMC_A23/PE2_1") (pintype "input"))
    )
    (net (code "64") (name "/PE3") (class "Default")
      (node (ref "U17") (pin "2") (pinfunction "TRACED0/FSMC_A19/PE3_2") (pintype "input"))
    )
    (net (code "65") (name "/PE4") (class "Default")
      (node (ref "U17") (pin "3") (pinfunction "TRACED1/FSMC_A20/PE4_3") (pintype "input"))
    )
    (net (code "66") (name "/PE5") (class "Default")
      (node (ref "U17") (pin "4") (pinfunction "TRACED2/FSMC_A21/PE5_4") (pintype "input"))
    )
    (net (code "67") (name "/PE6") (class "Default")
      (node (ref "U17") (pin "5") (pinfunction "TRACED3/FSMC_A22/PE6_5") (pintype "input"))
    )
    (net (code "68") (name "/PE7") (class "Default")
      (node (ref "U17") (pin "38") (pinfunction "TIM1_ETR/FSMC_D4/PE7_38") (pintype "input"))
    )
    (net (code "69") (name "/PE8") (class "Default")
      (node (ref "U17") (pin "39") (pinfunction "TIM1_CH1N/FSMC_D5/PE8_39") (pintype "input"))
    )
    (net (code "70") (name "/PE9") (class "Default")
      (node (ref "U17") (pin "40") (pinfunction "TIM1_CH1/FSMC_D6/PE9_40") (pintype "input"))
    )
    (net (code "71") (name "/PE10") (class "Default")
      (node (ref "U17") (pin "41") (pinfunction "TIM1_CH2N/FSMC_D7/PE10_41") (pintype "input"))
    )
    (net (code "72") (name "/PE11") (class "Default")
      (node (ref "U17") (pin "42") (pinfunction "TIM1_CH2/FSMC_D8/PE11_42") (pintype "input"))
    )
    (net (code "73") (name "/PE12") (class "Default")
      (node (ref "U17") (pin "43") (pinfunction "TIM1_CH3N/FSMC_D9/PE12_43") (pintype "input"))
    )
    (net (code "74") (name "/PE13") (class "Default")
      (node (ref "U17") (pin "44") (pinfunction "TIM1_CH3/FSMC_D10/PE13_44") (pintype "input"))
    )
    (net (code "75") (name "/PE14") (class "Default")
      (node (ref "U17") (pin "45") (pinfunction "TIM1_CH4/FSMC_D11/PE14_45") (pintype "input"))
    )
    (net (code "76") (name "/PE15") (class "Default")
      (node (ref "U17") (pin "46") (pinfunction "TIM1_BKIN/FSMC_D12/PE15_46") (pintype "input"))
    )
    (net (code "77") (name "/RESET") (class "Default")
      (node (ref "C46") (pin "2") (pinfunction "2_2") (pintype "unspecified"))
      (node (ref "R42") (pin "1") (pinfunction "1_1") (pintype "input"))
      (node (ref "SW7") (pin "2") (pinfunction "2_2") (pintype "unspecified"))
      (node (ref "U17") (pin "14") (pinfunction "NRST_14") (pintype "input"))
    )
    (net (code "78") (name "/SWCLK") (class "Default")
      (node (ref "U17") (pin "76") (pinfunction "PA14/JTCK/SWCLK_76") (pintype "input"))
      (node (ref "U18") (pin "5") (pinfunction "5_5") (pintype "input"))
    )
    (net (code "79") (name "/SWDIO") (class "Default")
      (node (ref "U17") (pin "72") (pinfunction "PA13/JTMS/SWDIO_72") (pintype "input"))
      (node (ref "U18") (pin "4") (pinfunction "4_4") (pintype "input"))
    )
    (net (code "80") (name "/USART1_RX") (class "Default")
      (node (ref "U17") (pin "69") (pinfunction "PA10/USART1_RX/TIM1_CH2_69") (pintype "input"))
      (node (ref "U26") (pin "6") (pinfunction "TXD_6") (pintype "unspecified"))
    )
    (net (code "81") (name "/USART1_TX") (class "Default")
      (node (ref "U17") (pin "68") (pinfunction "PA9/USART1_TX/TIM1_CH2_68") (pintype "input"))
      (node (ref "U26") (pin "7") (pinfunction "RXD_7") (pintype "unspecified"))
    )
    (net (code "82") (name "/USB_D+") (class "Default")
      (node (ref "U26") (pin "1") (pinfunction "UD+_1") (pintype "unspecified"))
      (node (ref "USB3") (pin "A6") (pinfunction "DP1_A6") (pintype "unspecified"))
      (node (ref "USB3") (pin "B6") (pinfunction "DP2_B6") (pintype "unspecified"))
    )
    (net (code "83") (name "/USB_D-") (class "Default")
      (node (ref "U26") (pin "2") (pinfunction "UD-_2") (pintype "unspecified"))
      (node (ref "USB3") (pin "A7") (pinfunction "DN1_A7") (pintype "unspecified"))
      (node (ref "USB3") (pin "B7") (pinfunction "DN2_B7") (pintype "unspecified"))
    )
    (net (code "84") (name "3.3V") (class "Default")
      (node (ref "C1") (pin "2") (pinfunction "2_2") (pintype "unspecified"))
      (node (ref "C2") (pin "2") (pinfunction "2_2") (pintype "unspecified"))
      (node (ref "C23") (pin "2") (pinfunction "2_2") (pintype "unspecified"))
      (node (ref "C26") (pin "2") (pinfunction "2_2") (pintype "unspecified"))
      (node (ref "C42") (pin "2") (pinfunction "2_2") (pintype "unspecified"))
      (node (ref "C43") (pin "2") (pinfunction "2_2") (pintype "unspecified"))
      (node (ref "C44") (pin "2") (pinfunction "2_2") (pintype "unspecified"))
      (node (ref "C45") (pin "2") (pinfunction "2_2") (pintype "unspecified"))
      (node (ref "C52") (pin "1") (pinfunction "1_1") (pintype "unspecified"))
      (node (ref "C53") (pin "2") (pinfunction "2_2") (pintype "unspecified"))
      (node (ref "C54") (pin "2") (pinfunction "2_2") (pintype "unspecified"))
      (node (ref "C57") (pin "1") (pinfunction "1_1") (pintype "input"))
      (node (ref "C58") (pin "1") (pinfunction "1_1") (pintype "input"))
      (node (ref "FPC2") (pin "8") (pinfunction "8_8") (pintype "unspecified"))
      (node (ref "FPC2") (pin "9") (pinfunction "9_9") (pintype "unspecified"))
      (node (ref "R10") (pin "2") (pinfunction "2_2") (pintype "unspecified"))
      (node (ref "R3") (pin "1") (pinfunction "1_1") (pintype "unspecified"))
      (node (ref "R4") (pin "1") (pinfunction "1_1") (pintype "unspecified"))
      (node (ref "R42") (pin "2") (pinfunction "2_2") (pintype "input"))
      (node (ref "R48") (pin "2") (pinfunction "2_2") (pintype "unspecified"))
      (node (ref "R5") (pin "1") (pinfunction "1_1") (pintype "unspecified"))
      (node (ref "R50") (pin "1") (pinfunction "1_1") (pintype "unspecified"))
      (node (ref "R51") (pin "1") (pinfunction "1_1") (pintype "unspecified"))
      (node (ref "R52") (pin "2") (pinfunction "2_2") (pintype "unspecified"))
      (node (ref "R53") (pin "2") (pinfunction "2_2") (pintype "unspecified"))
      (node (ref "R6") (pin "2") (pinfunction "2_2") (pintype "unspecified"))
      (node (ref "R7") (pin "2") (pinfunction "2_2") (pintype "unspecified"))
      (node (ref "U1") (pin "4") (pinfunction "VDD_4") (pintype "unspecified"))
      (node (ref "U17") (pin "100") (pinfunction "VDD_3_100") (pintype "input"))
      (node (ref "U17") (pin "11") (pinfunction "VDD_5_11") (pintype "input"))
      (node (ref "U17") (pin "19") (pinfunction "VDD_19") (pintype "input"))
      (node (ref "U17") (pin "21") (pinfunction "VREF+_21") (pintype "input"))
      (node (ref "U17") (pin "22") (pinfunction "VDDA_22") (pintype "input"))
      (node (ref "U17") (pin "28") (pinfunction "VDD_4_28") (pintype "input"))
      (node (ref "U17") (pin "50") (pinfunction "VDD_1_50") (pintype "input"))
      (node (ref "U17") (pin "6") (pinfunction "VBAT_6") (pintype "input"))
      (node (ref "U17") (pin "75") (pinfunction "VDD_2_75") (pintype "input"))
      (node (ref "U18") (pin "1") (pinfunction "1_1") (pintype "input"))
      (node (ref "U18") (pin "2") (pinfunction "2_2") (pintype "input"))
      (node (ref "U18") (pin "3") (pinfunction "3_3") (pintype "input"))
      (node (ref "U2") (pin "5") (pinfunction "VOUT_5") (pintype "unspecified"))
      (node (ref "U23") (pin "1") (pinfunction "+_1") (pintype "unspecified"))
      (node (ref "U24") (pin "1") (pinfunction "K_1") (pintype "unspecified"))
      (node (ref "U25") (pin "13") (pinfunction "VDD_13") (pintype "input"))
      (node (ref "U25") (pin "8") (pinfunction "VLOGIC_8") (pintype "input"))
      (node (ref "U26") (pin "5") (pinfunction "VCC_5") (pintype "unspecified"))
      (node (ref "U26") (pin "8") (pinfunction "V3_8") (pintype "unspecified"))
    )
    (net (code "85") (name "3.7V") (class "Default")
      (node (ref "C11") (pin "2") (pinfunction "2_2") (pintype "unspecified"))
      (node (ref "C22") (pin "2") (pinfunction "2_2") (pintype "unspecified"))
      (node (ref "R55") (pin "2") (pinfunction "2_2") (pintype "input"))
      (node (ref "U13") (pin "2") (pinfunction "2_2") (pintype "input"))
      (node (ref "U2") (pin "1") (pinfunction "VIN_1") (pintype "unspecified"))
      (node (ref "U2") (pin "3") (pinfunction "CE_3") (pintype "unspecified"))
      (node (ref "U22") (pin "1") (pinfunction "VIN_1") (pintype "unspecified"))
      (node (ref "U22") (pin "3") (pinfunction "CE_3") (pintype "unspecified"))
    )
    (net (code "86") (name "5V") (class "Default")
      (node (ref "C14") (pin "1") (pinfunction "1_1") (pintype "input"))
      (node (ref "LED10") (pin "2") (pinfunction "A_2") (pintype "input"))
      (node (ref "LED9") (pin "2") (pinfunction "A_2") (pintype "input"))
      (node (ref "R12") (pin "2") (pinfunction "2_2") (pintype "unspecified"))
      (node (ref "R57") (pin "2") (pinfunction "2_2") (pintype "input"))
      (node (ref "U21") (pin "4") (pinfunction "VCC_4") (pintype "input"))
      (node (ref "U21") (pin "8") (pinfunction "CE_8") (pintype "input"))
      (node (ref "USB3") (pin "A4") (pinfunction "VBUS_A4") (pintype "unspecified"))
      (node (ref "USB3") (pin "A9") (pinfunction "VBUS_A9") (pintype "unspecified"))
      (node (ref "USB3") (pin "B4") (pinfunction "VBUS_B4") (pintype "unspecified"))
      (node (ref "USB3") (pin "B9") (pinfunction "VBUS_B9") (pintype "unspecified"))
    )
    (net (code "87") (name "GND") (class "Default")
      (node (ref "C1") (pin "1") (pinfunction "1_1") (pintype "unspecified"))
      (node (ref "C11") (pin "1") (pinfunction "1_1") (pintype "unspecified"))
      (node (ref "C14") (pin "2") (pinfunction "2_2") (pintype "input"))
      (node (ref "C15") (pin "1") (pinfunction "1_1") (pintype "input"))
      (node (ref "C2") (pin "1") (pinfunction "1_1") (pintype "unspecified"))
      (node (ref "C20") (pin "1") (pinfunction "1_1") (pintype "unspecified"))
      (node (ref "C21") (pin "1") (pinfunction "1_1") (pintype "unspecified"))
      (node (ref "C22") (pin "1") (pinfunction "1_1") (pintype "unspecified"))
      (node (ref "C23") (pin "1") (pinfunction "1_1") (pintype "unspecified"))
      (node (ref "C25") (pin "1") (pinfunction "1_1") (pintype "unspecified"))
      (node (ref "C26") (pin "1") (pinfunction "1_1") (pintype "unspecified"))
      (node (ref "C3") (pin "1") (pinfunction "1_1") (pintype "input"))
      (node (ref "C4") (pin "1") (pinfunction "1_1") (pintype "input"))
      (node (ref "C40") (pin "1") (pinfunction "1_1") (pintype "input"))
      (node (ref "C41") (pin "1") (pinfunction "1_1") (pintype "input"))
      (node (ref "C42") (pin "1") (pinfunction "1_1") (pintype "unspecified"))
      (node (ref "C43") (pin "1") (pinfunction "1_1") (pintype "unspecified"))
      (node (ref "C44") (pin "1") (pinfunction "1_1") (pintype "unspecified"))
      (node (ref "C45") (pin "1") (pinfunction "1_1") (pintype "unspecified"))
      (node (ref "C46") (pin "1") (pinfunction "1_1") (pintype "unspecified"))
      (node (ref "C47") (pin "1") (pinfunction "1_1") (pintype "unspecified"))
      (node (ref "C48") (pin "1") (pinfunction "1_1") (pintype "unspecified"))
      (node (ref "C49") (pin "2") (pinfunction "2_2") (pintype "unspecified"))
      (node (ref "C52") (pin "2") (pinfunction "2_2") (pintype "unspecified"))
      (node (ref "C53") (pin "1") (pinfunction "1_1") (pintype "unspecified"))
      (node (ref "C54") (pin "1") (pinfunction "1_1") (pintype "unspecified"))
      (node (ref "C57") (pin "2") (pinfunction "2_2") (pintype "input"))
      (node (ref "C58") (pin "2") (pinfunction "2_2") (pintype "input"))
      (node (ref "CN1") (pin "1") (pinfunction "1_1") (pintype "unspecified"))
      (node (ref "CN1") (pin "5") (pinfunction "5_5") (pintype "unspecified"))
      (node (ref "FPC2") (pin "1") (pinfunction "1_1") (pintype "unspecified"))
      (node (ref "H1") (pin "2") (pinfunction "2_2") (pintype "input"))
      (node (ref "LED3") (pin "2") (pinfunction "2_2") (pintype "unspecified"))
      (node (ref "Q3") (pin "2") (pinfunction "E_2") (pintype "input"))
      (node (ref "R15") (pin "1") (pinfunction "1_1") (pintype "unspecified"))
      (node (ref "R31") (pin "2") (pinfunction "2_2") (pintype "input"))
      (node (ref "R40") (pin "2") (pinfunction "2_2") (pintype "input"))
      (node (ref "R41") (pin "2") (pinfunction "2_2") (pintype "input"))
      (node (ref "R44") (pin "1") (pinfunction "1_1") (pintype "unspecified"))
      (node (ref "R45") (pin "2") (pinfunction "2_2") (pintype "unspecified"))
      (node (ref "R46") (pin "1") (pinfunction "1_1") (pintype "unspecified"))
      (node (ref "R49") (pin "1") (pinfunction "1_1") (pintype "input"))
      (node (ref "R54") (pin "1") (pinfunction "1_1") (pintype "input"))
      (node (ref "R56") (pin "1") (pinfunction "1_1") (pintype "input"))
      (node (ref "R58") (pin "1") (pinfunction "1_1") (pintype "unspecified"))
      (node (ref "SW1") (pin "4") (pinfunction "C_4") (pintype "unspecified"))
      (node (ref "SW1") (pin "5") (pinfunction "C_5") (pintype "unspecified"))
      (node (ref "SW7") (pin "1") (pinfunction "1_1") (pintype "unspecified"))
      (node (ref "U1") (pin "10") (pinfunction "GND_10") (pintype "unspecified"))
      (node (ref "U1") (pin "11") (pinfunction "GND_11") (pintype "unspecified"))
      (node (ref "U1") (pin "12") (pinfunction "GND_12") (pintype "unspecified"))
      (node (ref "U1") (pin "13") (pinfunction "GND_13") (pintype "unspecified"))
      (node (ref "U1") (pin "6") (pinfunction "VSS_6") (pintype "unspecified"))
      (node (ref "U10") (pin "9") (pinfunction "GND_9") (pintype "unspecified"))
      (node (ref "U13") (pin "4") (pinfunction "4_4") (pintype "input"))
      (node (ref "U17") (pin "10") (pinfunction "VSS_5_10") (pintype "input"))
      (node (ref "U17") (pin "20") (pinfunction "VREF-_20") (pintype "input"))
      (node (ref "U17") (pin "27") (pinfunction "VSS_4_27") (pintype "input"))
      (node (ref "U17") (pin "74") (pinfunction "VSS_2_74") (pintype "input"))
      (node (ref "U17") (pin "99") (pinfunction "VSS_3_99") (pintype "input"))
      (node (ref "U18") (pin "6") (pinfunction "6_6") (pintype "input"))
      (node (ref "U18") (pin "7") (pinfunction "7_7") (pintype "input"))
      (node (ref "U18") (pin "8") (pinfunction "8_8") (pintype "input"))
      (node (ref "U2") (pin "2") (pinfunction "VSS_2") (pintype "unspecified"))
      (node (ref "U21") (pin "1") (pinfunction "TEMP_1") (pintype "input"))
      (node (ref "U21") (pin "3") (pinfunction "GND_3") (pintype "input"))
      (node (ref "U21") (pin "9") (pinfunction "EP_9") (pintype "input"))
      (node (ref "U22") (pin "2") (pinfunction "VSS_2") (pintype "unspecified"))
      (node (ref "U25") (pin "1") (pinfunction "CLKIN_1") (pintype "input"))
      (node (ref "U25") (pin "11") (pinfunction "FSYNC_11") (pintype "input"))
      (node (ref "U25") (pin "18") (pinfunction "GND_18") (pintype "input"))
      (node (ref "U25") (pin "25") (pinfunction "GND_25") (pintype "input"))
      (node (ref "U26") (pin "3") (pinfunction "GND_3") (pintype "unspecified"))
      (node (ref "U27") (pin "2") (pinfunction "S_2") (pintype "unspecified"))
      (node (ref "U7") (pin "2") (pinfunction "S_2") (pintype "unspecified"))
      (node (ref "USB3") (pin "1") (pinfunction "EP_1") (pintype "unspecified"))
      (node (ref "USB3") (pin "2") (pinfunction "EP_2") (pintype "unspecified"))
      (node (ref "USB3") (pin "3") (pinfunction "EP_3") (pintype "unspecified"))
      (node (ref "USB3") (pin "4") (pinfunction "EP_4") (pintype "unspecified"))
      (node (ref "USB3") (pin "A1") (pinfunction "GND_A1") (pintype "unspecified"))
      (node (ref "USB3") (pin "A12") (pinfunction "GND_A12") (pintype "unspecified"))
      (node (ref "USB3") (pin "B1") (pinfunction "GND_B1") (pintype "unspecified"))
      (node (ref "USB3") (pin "B12") (pinfunction "GND_B12") (pintype "unspecified"))
      (node (ref "X3") (pin "2") (pinfunction "GND_2") (pintype "input"))
      (node (ref "X3") (pin "4") (pinfunction "GND_4") (pintype "input"))
    )
    (net (code "88") (name "Net-(C3-Pad2)") (class "Default")
      (node (ref "C3") (pin "2") (pinfunction "2_2") (pintype "input"))
      (node (ref "C50") (pin "2") (pinfunction "2_2") (pintype "input"))
      (node (ref "R1") (pin "1") (pinfunction "1_1") (pintype "input"))
    )
    (net (code "89") (name "Net-(C4-Pad2)") (class "Default")
      (node (ref "C4") (pin "2") (pinfunction "2_2") (pintype "input"))
      (node (ref "C51") (pin "2") (pinfunction "2_2") (pintype "input"))
      (node (ref "R2") (pin "1") (pinfunction "1_1") (pintype "input"))
    )
    (net (code "90") (name "Net-(C50-Pad1)") (class "Default")
      (node (ref "C50") (pin "1") (pinfunction "1_1") (pintype "input"))
      (node (ref "CN1") (pin "3") (pinfunction "3_3") (pintype "unspecified"))
    )
    (net (code "91") (name "Net-(C51-Pad1)") (class "Default")
      (node (ref "C51") (pin "1") (pinfunction "1_1") (pintype "input"))
      (node (ref "CN1") (pin "2") (pinfunction "2_2") (pintype "unspecified"))
      (node (ref "CN1") (pin "4") (pinfunction "4_4") (pintype "unspecified"))
    )
    (net (code "92") (name "Net-(LED2-Pad1)") (class "Default")
      (node (ref "LED2") (pin "1") (pinfunction "1_1") (pintype "unspecified"))
      (node (ref "R52") (pin "1") (pinfunction "1_1") (pintype "unspecified"))
    )
    (net (code "93") (name "Net-(LED3-Pad1)") (class "Default")
      (node (ref "LED3") (pin "1") (pinfunction "1_1") (pintype "unspecified"))
      (node (ref "R12") (pin "1") (pinfunction "1_1") (pintype "unspecified"))
    )
    (net (code "94") (name "Net-(LED4-Pad1)") (class "Default")
      (node (ref "LED4") (pin "1") (pinfunction "1_1") (pintype "unspecified"))
      (node (ref "R7") (pin "1") (pinfunction "1_1") (pintype "unspecified"))
    )
    (net (code "95") (name "Net-(LED5-Pad1)") (class "Default")
      (node (ref "LED5") (pin "1") (pinfunction "1_1") (pintype "unspecified"))
      (node (ref "R53") (pin "1") (pinfunction "1_1") (pintype "unspecified"))
    )
    (net (code "96") (name "Net-(LED9-C)") (class "Default")
      (node (ref "LED9") (pin "1") (pinfunction "C_1") (pintype "input"))
      (node (ref "R29") (pin "1") (pinfunction "1_1") (pintype "input"))
    )
    (net (code "97") (name "Net-(LED10-C)") (class "Default")
      (node (ref "LED10") (pin "1") (pinfunction "C_1") (pintype "input"))
      (node (ref "R30") (pin "1") (pinfunction "1_1") (pintype "input"))
    )
    (net (code "98") (name "Net-(LED11-C)") (class "Default")
      (node (ref "LED11") (pin "1") (pinfunction "C_1") (pintype "input"))
      (node (ref "R41") (pin "1") (pinfunction "1_1") (pintype "input"))
    )
    (net (code "99") (name "Net-(LED12-Pad1)") (class "Default")
      (node (ref "LED12") (pin "1") (pinfunction "1_1") (pintype "unspecified"))
      (node (ref "R6") (pin "1") (pinfunction "1_1") (pintype "unspecified"))
    )
    (net (code "100") (name "Net-(Q3-B)") (class "Default")
      (node (ref "Q3") (pin "1") (pinfunction "B_1") (pintype "input"))
      (node (ref "R46") (pin "2") (pinfunction "2_2") (pintype "unspecified"))
      (node (ref "R47") (pin "2") (pinfunction "2_2") (pintype "unspecified"))
    )
    (net (code "101") (name "Net-(Q3-C)") (class "Default")
      (node (ref "Q3") (pin "3") (pinfunction "C_3") (pintype "input"))
      (node (ref "U23") (pin "2") (pinfunction "-_2") (pintype "unspecified"))
      (node (ref "U24") (pin "2") (pinfunction "A_2") (pintype "unspecified"))
    )
    (net (code "102") (name "Net-(U17-BOOT0)") (class "Default")
      (node (ref "R40") (pin "1") (pinfunction "1_1") (pintype "input"))
      (node (ref "U17") (pin "94") (pinfunction "BOOT0_94") (pintype "input"))
    )
    (net (code "103") (name "Net-(U17-VCAP_1)") (class "Default")
      (node (ref "C40") (pin "2") (pinfunction "2_2") (pintype "input"))
      (node (ref "U17") (pin "49") (pinfunction "VCAP_1_49") (pintype "input"))
    )
    (net (code "104") (name "Net-(U17-VCAP_2)") (class "Default")
      (node (ref "C41") (pin "2") (pinfunction "2_2") (pintype "input"))
      (node (ref "U17") (pin "73") (pinfunction "VCAP_2_73") (pintype "input"))
    )
    (net (code "105") (name "Net-(U21-CHRG#)") (class "Default")
      (node (ref "R29") (pin "2") (pinfunction "2_2") (pintype "input"))
      (node (ref "U21") (pin "7") (pinfunction "CHRG#_7") (pintype "input"))
    )
    (net (code "106") (name "Net-(U21-PROG)") (class "Default")
      (node (ref "R31") (pin "1") (pinfunction "1_1") (pintype "input"))
      (node (ref "U21") (pin "2") (pinfunction "PROG_2") (pintype "input"))
    )
    (net (code "107") (name "Net-(U21-STDBY#)") (class "Default")
      (node (ref "R30") (pin "2") (pinfunction "2_2") (pintype "input"))
      (node (ref "U21") (pin "6") (pinfunction "STDBY#_6") (pintype "input"))
    )
    (net (code "108") (name "Net-(U25-AD0)") (class "Default")
      (node (ref "R49") (pin "2") (pinfunction "2_2") (pintype "input"))
      (node (ref "U25") (pin "9") (pinfunction "AD0_9") (pintype "input"))
    )
    (net (code "109") (name "Net-(U25-CPOUT)") (class "Default")
      (node (ref "C49") (pin "1") (pinfunction "1_1") (pintype "unspecified"))
      (node (ref "U25") (pin "20") (pinfunction "CPOUT_20") (pintype "input"))
    )
    (net (code "110") (name "Net-(U25-REGOUT)") (class "Default")
      (node (ref "C25") (pin "2") (pinfunction "2_2") (pintype "unspecified"))
      (node (ref "U25") (pin "10") (pinfunction "REGOUT_10") (pintype "input"))
    )
    (net (code "111") (name "Net-(USB3-CC1)") (class "Default")
      (node (ref "R44") (pin "2") (pinfunction "2_2") (pintype "unspecified"))
      (node (ref "USB3") (pin "A5") (pinfunction "CC1_A5") (pintype "unspecified"))
    )
    (net (code "112") (name "Net-(USB3-CC2)") (class "Default")
      (node (ref "R45") (pin "1") (pinfunction "1_1") (pintype "unspecified"))
      (node (ref "USB3") (pin "B5") (pinfunction "CC2_B5") (pintype "unspecified"))
    )
    (net (code "113") (name "PB8") (class "Default")
      (node (ref "R48") (pin "1") (pinfunction "1_1") (pintype "unspecified"))
      (node (ref "U17") (pin "95") (pinfunction "(I2C1_SCL/CANRX)/SDIO_D4/TIM4_CH3/PB8_95") (pintype "input"))
      (node (ref "U25") (pin "23") (pinfunction "SCL_23") (pintype "input"))
    )
    (net (code "114") (name "PB9") (class "Default")
      (node (ref "R10") (pin "1") (pinfunction "1_1") (pintype "unspecified"))
      (node (ref "U17") (pin "96") (pinfunction "(I2C1_SDA/CANTX)/SDIO_D5/TIM4_CH4/PB9_96") (pintype "input"))
      (node (ref "U25") (pin "24") (pinfunction "SDA_24") (pintype "input"))
    )
    (net (code "115") (name "VIN") (class "Default")
      (node (ref "C15") (pin "2") (pinfunction "2_2") (pintype "input"))
      (node (ref "H1") (pin "1") (pinfunction "1_1") (pintype "input"))
      (node (ref "U13") (pin "3") (pinfunction "3_3") (pintype "input"))
      (node (ref "U21") (pin "5") (pinfunction "BAT_5") (pintype "input"))
    )
    (net (code "116") (name "WF3.3V") (class "Default")
      (node (ref "C20") (pin "2") (pinfunction "2_2") (pintype "unspecified"))
      (node (ref "C21") (pin "2") (pinfunction "2_2") (pintype "unspecified"))
      (node (ref "U10") (pin "8") (pinfunction "VCC_8") (pintype "unspecified"))
      (node (ref "U22") (pin "5") (pinfunction "VOUT_5") (pintype "unspecified"))
    )
    (net (code "117") (name "unconnected-(FPC2-Pad7)") (class "Default")
      (node (ref "FPC2") (pin "7") (pinfunction "7_7") (pintype "unspecified+no_connect"))
    )
    (net (code "118") (name "unconnected-(FPC2-Pad11)") (class "Default")
      (node (ref "FPC2") (pin "11") (pinfunction "11_11") (pintype "unspecified"))
    )
    (net (code "119") (name "unconnected-(FPC2-Pad12)") (class "Default")
      (node (ref "FPC2") (pin "12") (pinfunction "12_12") (pintype "unspecified"))
    )
    (net (code "120") (name "unconnected-(SCREW1-Pad1)") (class "Default")
      (node (ref "SCREW1") (pin "1") (pinfunction "1_1") (pintype "input"))
    )
    (net (code "121") (name "unconnected-(SCREW2-Pad1)") (class "Default")
      (node (ref "SCREW2") (pin "1") (pinfunction "1_1") (pintype "input"))
    )
    (net (code "122") (name "unconnected-(SCREW3-Pad1)") (class "Default")
      (node (ref "SCREW3") (pin "1") (pinfunction "1_1") (pintype "input"))
    )
    (net (code "123") (name "unconnected-(SCREW4-Pad1)") (class "Default")
      (node (ref "SCREW4") (pin "1") (pinfunction "1_1") (pintype "input"))
    )
    (net (code "124") (name "unconnected-(SW7-Pad3)") (class "Default")
      (node (ref "SW7") (pin "3") (pinfunction "3_3") (pintype "unspecified"))
    )
    (net (code "125") (name "unconnected-(SW7-Pad4)") (class "Default")
      (node (ref "SW7") (pin "4") (pinfunction "4_4") (pintype "unspecified"))
    )
    (net (code "126") (name "unconnected-(U1-CD-Pad9)") (class "Default")
      (node (ref "U1") (pin "9") (pinfunction "CD_9") (pintype "unspecified+no_connect"))
    )
    (net (code "127") (name "unconnected-(U2-NC-Pad4)") (class "Default")
      (node (ref "U2") (pin "4") (pinfunction "NC_4") (pintype "unspecified+no_connect"))
    )
    (net (code "128") (name "unconnected-(U10-EN-Pad7)") (class "Default")
      (node (ref "U10") (pin "7") (pinfunction "EN_7") (pintype "unspecified"))
    )
    (net (code "129") (name "unconnected-(U10-IO0-Pad5)") (class "Default")
      (node (ref "U10") (pin "5") (pinfunction "IO0_5") (pintype "unspecified"))
    )
    (net (code "130") (name "unconnected-(U10-IO2-Pad6)") (class "Default")
      (node (ref "U10") (pin "6") (pinfunction "IO2_6") (pintype "unspecified"))
    )
    (net (code "131") (name "unconnected-(U10-IO4-Pad4)") (class "Default")
      (node (ref "U10") (pin "4") (pinfunction "IO4_4") (pintype "unspecified"))
    )
    (net (code "132") (name "unconnected-(U10-IO12-Pad3)") (class "Default")
      (node (ref "U10") (pin "3") (pinfunction "IO12_3") (pintype "unspecified"))
    )
    (net (code "133") (name "unconnected-(U10-IO14-Pad2)") (class "Default")
      (node (ref "U10") (pin "2") (pinfunction "IO14_2") (pintype "unspecified"))
    )
    (net (code "134") (name "unconnected-(U10-IO16-Pad1)") (class "Default")
      (node (ref "U10") (pin "1") (pinfunction "IO16_1") (pintype "unspecified"))
    )
    (net (code "135") (name "unconnected-(U10-RST-Pad12)") (class "Default")
      (node (ref "U10") (pin "12") (pinfunction "RST_12") (pintype "unspecified"))
    )
    (net (code "136") (name "unconnected-(U13-Pad1)") (class "Default")
      (node (ref "U13") (pin "1") (pinfunction "1_1") (pintype "input+no_connect"))
    )
    (net (code "137") (name "unconnected-(U17-PC14{slash}OSC32_IN-Pad8)") (class "Default")
      (node (ref "U17") (pin "8") (pinfunction "PC14/OSC32_IN_8") (pintype "input+no_connect"))
    )
    (net (code "138") (name "unconnected-(U17-PC15{slash}OSC32_OUT-Pad9)") (class "Default")
      (node (ref "U17") (pin "9") (pinfunction "PC15/OSC32_OUT_9") (pintype "input+no_connect"))
    )
    (net (code "139") (name "unconnected-(U18-Pad10)") (class "Default")
      (node (ref "U18") (pin "10") (pinfunction "10_10") (pintype "input"))
    )
    (net (code "140") (name "unconnected-(U18-Pad11)") (class "Default")
      (node (ref "U18") (pin "11") (pinfunction "11_11") (pintype "input"))
    )
    (net (code "141") (name "unconnected-(U22-NC-Pad4)") (class "Default")
      (node (ref "U22") (pin "4") (pinfunction "NC_4") (pintype "unspecified+no_connect"))
    )
    (net (code "142") (name "unconnected-(U23-NC-Pad3)") (class "Default")
      (node (ref "U23") (pin "3") (pinfunction "NC_3") (pintype "unspecified"))
    )
    (net (code "143") (name "unconnected-(U25-AUX_CL-Pad7)") (class "Default")
      (node (ref "U25") (pin "7") (pinfunction "AUX_CL_7") (pintype "input+no_connect"))
    )
    (net (code "144") (name "unconnected-(U25-AUX_DA-Pad6)") (class "Default")
      (node (ref "U25") (pin "6") (pinfunction "AUX_DA_6") (pintype "input+no_connect"))
    )
    (net (code "145") (name "unconnected-(U25-INT-Pad12)") (class "Default")
      (node (ref "U25") (pin "12") (pinfunction "INT_12") (pintype "input+no_connect"))
    )
    (net (code "146") (name "unconnected-(U25-NC-Pad2)") (class "Default")
      (node (ref "U25") (pin "2") (pinfunction "NC_2") (pintype "input+no_connect"))
    )
    (net (code "147") (name "unconnected-(U25-NC-Pad3)") (class "Default")
      (node (ref "U25") (pin "3") (pinfunction "NC_3") (pintype "input+no_connect"))
    )
    (net (code "148") (name "unconnected-(U25-NC-Pad4)") (class "Default")
      (node (ref "U25") (pin "4") (pinfunction "NC_4") (pintype "input+no_connect"))
    )
    (net (code "149") (name "unconnected-(U25-NC-Pad5)") (class "Default")
      (node (ref "U25") (pin "5") (pinfunction "NC_5") (pintype "input+no_connect"))
    )
    (net (code "150") (name "unconnected-(U25-NC-Pad14)") (class "Default")
      (node (ref "U25") (pin "14") (pinfunction "NC_14") (pintype "input+no_connect"))
    )
    (net (code "151") (name "unconnected-(U25-NC-Pad15)") (class "Default")
      (node (ref "U25") (pin "15") (pinfunction "NC_15") (pintype "input+no_connect"))
    )
    (net (code "152") (name "unconnected-(U25-NC-Pad16)") (class "Default")
      (node (ref "U25") (pin "16") (pinfunction "NC_16") (pintype "input+no_connect"))
    )
    (net (code "153") (name "unconnected-(U25-NC-Pad17)") (class "Default")
      (node (ref "U25") (pin "17") (pinfunction "NC_17") (pintype "input+no_connect"))
    )
    (net (code "154") (name "unconnected-(U25-RESV-Pad19)") (class "Default")
      (node (ref "U25") (pin "19") (pinfunction "RESV_19") (pintype "input+no_connect"))
    )
    (net (code "155") (name "unconnected-(U25-RESV-Pad21)") (class "Default")
      (node (ref "U25") (pin "21") (pinfunction "RESV_21") (pintype "input+no_connect"))
    )
    (net (code "156") (name "unconnected-(U25-RESV-Pad22)") (class "Default")
      (node (ref "U25") (pin "22") (pinfunction "RESV_22") (pintype "input+no_connect"))
    )
    (net (code "157") (name "unconnected-(U26-RTS#-Pad4)") (class "Default")
      (node (ref "U26") (pin "4") (pinfunction "RTS#_4") (pintype "unspecified+no_connect"))
    )
    (net (code "158") (name "unconnected-(USB3-SUB1-PadA8)") (class "Default")
      (node (ref "USB3") (pin "A8") (pinfunction "SUB1_A8") (pintype "unspecified+no_connect"))
    )
    (net (code "159") (name "unconnected-(USB3-SUB2-PadB8)") (class "Default")
      (node (ref "USB3") (pin "B8") (pinfunction "SUB2_B8") (pintype "unspecified+no_connect"))
    )
  )
)
